# Servo_Tester.net
KiCad netlist of a schematic drawn in EAGLE
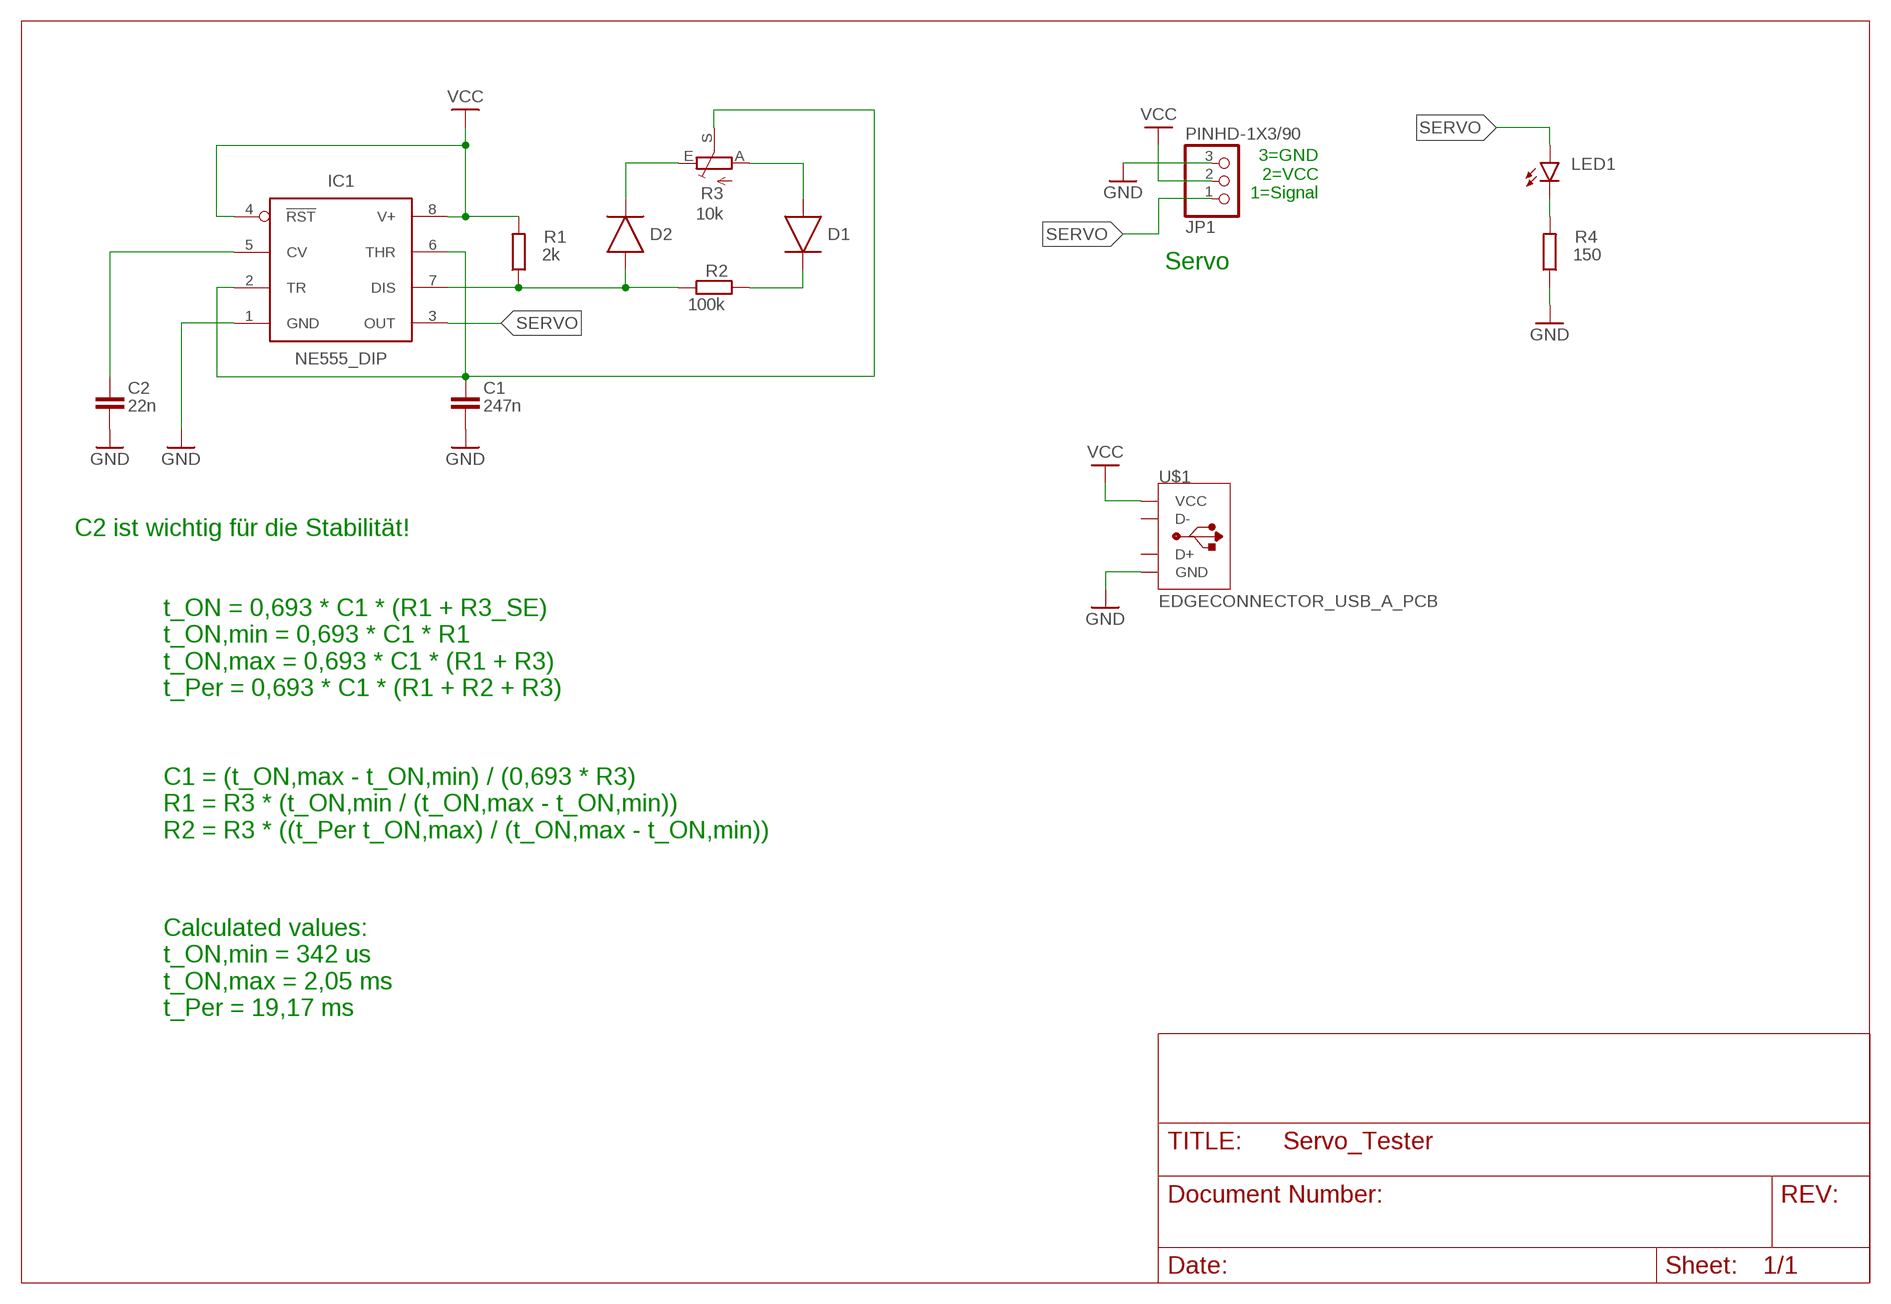
[diagram p0: schematic, sheet 1]

(export (version "E")
  (design (tool "Eeschema 10.0.6"))
  (components
    (comp (ref "C1")
      (value "247n")
      (footprint "eagle-import:CAPC2012X110")
      (libsource (lib "eagle-import") (part "CCHIP-0805(2012-METRIC)_"))
    )
    (comp (ref "C2")
      (value "22n")
      (footprint "eagle-import:CAPC2012X110")
      (libsource (lib "eagle-import") (part "CCHIP-0805(2012-METRIC)_"))
    )
    (comp (ref "D1")
      (value "DIODE_LL4148_SOD-80")
      (footprint "eagle-import:DIOMELF3516")
      (fields (field (name "MANUFACTURER") "ON Semiconductor "))
      (libsource (lib "eagle-import") (part "DIODE__SOD-80LL4148"))
    )
    (comp (ref "D2")
      (value "DIODE_LL4148_SOD-80")
      (footprint "eagle-import:DIOMELF3516")
      (fields (field (name "MANUFACTURER") "ON Semiconductor "))
      (libsource (lib "eagle-import") (part "DIODE__SOD-80LL4148"))
    )
    (comp (ref "IC1")
      (value "NE555_DIP")
      (footprint "eagle-import:DIP826W53P254L959H508Q8B")
      (fields
        (field (name "MANUFACTURER") "Renesas Electronics America Inc ")
        (field (name "MPN") "ICM7555IPAZ ")
      )
      (libsource (lib "eagle-import") (part "555_DIPICM7"))
    )
    (comp (ref "JP1")
      (value "PINHD-1X3/90")
      (footprint "eagle-import:1X03_90")
      (fields (field (name "MANUFACTURER") "Generic"))
      (libsource (lib "eagle-import") (part "PINHD-1X3/90"))
    )
    (comp (ref "LED1")
      (value "LEDCHIP-LED0805")
      (footprint "eagle-import:CHIP-LED0805")
      (libsource (lib "eagle-import") (part "LEDCHIP-LED0805"))
    )
    (comp (ref "R1")
      (value "2k")
      (footprint "eagle-import:R0805")
      (libsource (lib "eagle-import") (part "R-EU_R0805"))
    )
    (comp (ref "R2")
      (value "100k")
      (footprint "eagle-import:R0805")
      (libsource (lib "eagle-import") (part "R-EU_R0805"))
    )
    (comp (ref "R3")
      (value "10k")
      (footprint "eagle-import:LI15")
      (libsource (lib "eagle-import") (part "TRIM_EU-LI15"))
    )
    (comp (ref "R4")
      (value "150")
      (footprint "eagle-import:R0805")
      (libsource (lib "eagle-import") (part "R-EU_R0805"))
    )
    (comp (ref "U$1")
      (value "EDGECONNECTOR_USB_A_PCB")
      (footprint "eagle-import:EDGECONNECTOR_USB_A_PCB")
      (libsource (lib "eagle-import") (part "EDGECONNECTOR_USB_A_PCB"))
    )
  )
  (nets
    (net (code "1") (name "GND") (class "Default")
      (node (ref "C1") (pin "2") (pinfunction "2_2") (pintype "passive"))
      (node (ref "C2") (pin "2") (pinfunction "2_2") (pintype "passive"))
      (node (ref "IC1") (pin "1") (pinfunction "GND_1") (pintype "power_in"))
      (node (ref "JP1") (pin "3") (pinfunction "3_3") (pintype "passive"))
      (node (ref "R4") (pin "1") (pinfunction "1_1") (pintype "passive"))
      (node (ref "U$1") (pin "GND") (pinfunction "GND_GND") (pintype "power_in"))
    )
    (net (code "2") (name "Net-(D1-A)") (class "Default")
      (node (ref "D1") (pin "2") (pinfunction "A_2") (pintype "passive"))
      (node (ref "R3") (pin "A") (pinfunction "A_A") (pintype "passive"))
    )
    (net (code "3") (name "Net-(D1-C)") (class "Default")
      (node (ref "D1") (pin "1") (pinfunction "C_1") (pintype "passive"))
      (node (ref "R2") (pin "2") (pinfunction "2_2") (pintype "passive"))
    )
    (net (code "4") (name "Net-(D2-A)") (class "Default")
      (node (ref "D2") (pin "2") (pinfunction "A_2") (pintype "passive"))
      (node (ref "IC1") (pin "7") (pinfunction "DIS_7") (pintype "input"))
      (node (ref "R1") (pin "1") (pinfunction "1_1") (pintype "passive"))
      (node (ref "R2") (pin "1") (pinfunction "1_1") (pintype "passive"))
    )
    (net (code "5") (name "Net-(D2-C)") (class "Default")
      (node (ref "D2") (pin "1") (pinfunction "C_1") (pintype "passive"))
      (node (ref "R3") (pin "E") (pinfunction "E_E") (pintype "passive"))
    )
    (net (code "6") (name "Net-(IC1-CV)") (class "Default")
      (node (ref "C2") (pin "1") (pinfunction "1_1") (pintype "passive"))
      (node (ref "IC1") (pin "5") (pinfunction "CV_5") (pintype "input"))
    )
    (net (code "7") (name "Net-(IC1-THR)") (class "Default")
      (node (ref "C1") (pin "1") (pinfunction "1_1") (pintype "passive"))
      (node (ref "IC1") (pin "2") (pinfunction "TR_2") (pintype "input"))
      (node (ref "IC1") (pin "6") (pinfunction "THR_6") (pintype "input"))
      (node (ref "R3") (pin "S") (pinfunction "S_S") (pintype "passive"))
    )
    (net (code "8") (name "Net-(LED1-PadC)") (class "Default")
      (node (ref "LED1") (pin "C") (pinfunction "C_C") (pintype "passive"))
      (node (ref "R4") (pin "2") (pinfunction "2_2") (pintype "passive"))
    )
    (net (code "9") (name "SERVO") (class "Default")
      (node (ref "IC1") (pin "3") (pinfunction "OUT_3") (pintype "output"))
      (node (ref "JP1") (pin "1") (pinfunction "1_1") (pintype "passive"))
      (node (ref "LED1") (pin "A") (pinfunction "A_A") (pintype "passive"))
    )
    (net (code "10") (name "VCC") (class "Default")
      (node (ref "IC1") (pin "4") (pinfunction "~{RST}_4") (pintype "input"))
      (node (ref "IC1") (pin "8") (pinfunction "V+_8") (pintype "power_in"))
      (node (ref "JP1") (pin "2") (pinfunction "2_2") (pintype "passive"))
      (node (ref "R1") (pin "2") (pinfunction "2_2") (pintype "passive"))
      (node (ref "U$1") (pin "VCC") (pinfunction "VCC_VCC") (pintype "power_in"))
    )
    (net (code "11") (name "unconnected-(U$1-PadD+)") (class "Default")
      (node (ref "U$1") (pin "D+") (pinfunction "D+_D+") (pintype "bidirectional"))
    )
    (net (code "12") (name "unconnected-(U$1-PadD-)") (class "Default")
      (node (ref "U$1") (pin "D-") (pinfunction "D-_D-") (pintype "bidirectional"))
    )
  )
)
